# Temperatura_y_humedadC.net
KiCad netlist of a schematic drawn in EAGLE
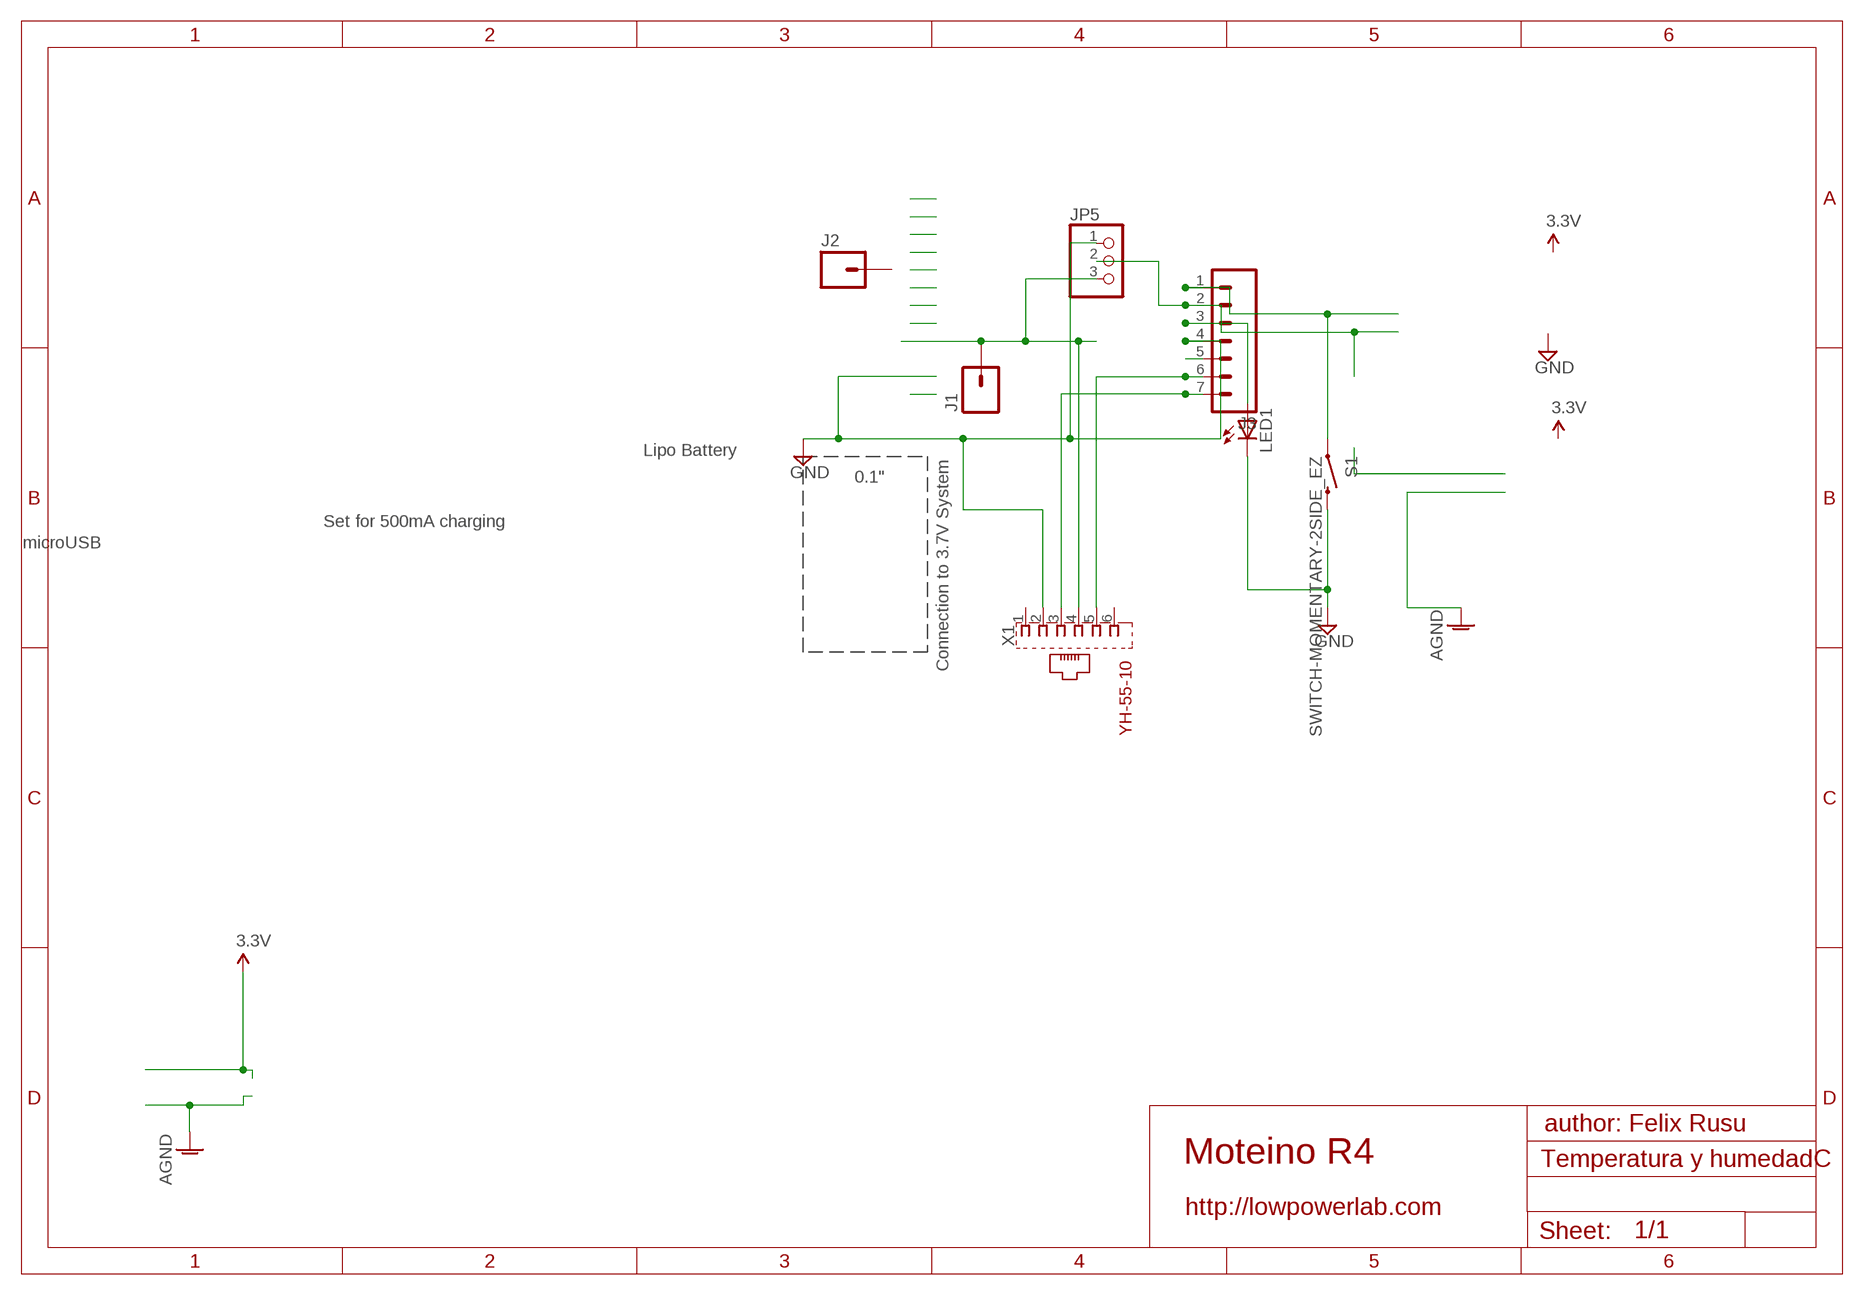
[diagram p0: schematic, sheet 1]

(export (version "E")
  (design (tool "Eeschema 10.0.6"))
  (components
    (comp (ref "J1")
      (value "M01PTH")
      (footprint "eagle-import:1X01")
      (libsource (lib "eagle-import") (part "M01PTH"))
    )
    (comp (ref "J2")
      (value "M01PTH")
      (footprint "eagle-import:1X01")
      (libsource (lib "eagle-import") (part "M01PTH"))
    )
    (comp (ref "J3")
      (value "M07")
      (footprint "eagle-import:1X07")
      (libsource (lib "eagle-import") (part "M07"))
    )
    (comp (ref "JP5")
      (value "PINHD-1X3")
      (footprint "eagle-import:1X03")
      (libsource (lib "eagle-import") (part "PINHD-1X3"))
    )
    (comp (ref "LED1")
      (value "LED3MM")
      (footprint "eagle-import:LED3MM")
      (libsource (lib "eagle-import") (part "LED3MM"))
    )
    (comp (ref "S1")
      (value "SWITCH-MOMENTARY-2SIDE_EZ")
      (footprint "eagle-import:TACTILE-PTH-SIDEEZ")
      (libsource (lib "eagle-import") (part "SWITCH-MOMENTARY-2SIDE_EZ"))
    )
    (comp (ref "X1")
      (value "YH-55-10")
      (footprint "eagle-import:YH-55-10")
      (libsource (lib "eagle-import") (part "YH-55-10"))
    )
  )
  (nets
    (net (code "3") (name "GND") (class "Default")
      (node (ref "J3") (pin "4") (pinfunction "4_4") (pintype "passive"))
      (node (ref "JP5") (pin "1") (pinfunction "1_1") (pintype "passive"))
      (node (ref "LED1") (pin "K") (pinfunction "C_K") (pintype "passive"))
      (node (ref "S1") (pin "2") (pinfunction "2_2") (pintype "passive"))
      (node (ref "X1") (pin "2") (pinfunction "2_2") (pintype "passive"))
    )
    (net (code "4") (name "Net-(J1-Pad1)") (class "Default")
      (node (ref "J1") (pin "1") (pinfunction "1_1") (pintype "passive"))
      (node (ref "JP5") (pin "3") (pinfunction "3_3") (pintype "passive"))
      (node (ref "X1") (pin "4") (pinfunction "4_4") (pintype "passive"))
    )
    (net (code "5") (name "Net-(J3-Pad1)") (class "Default")
      (node (ref "J3") (pin "1") (pinfunction "1_1") (pintype "passive"))
      (node (ref "S1") (pin "1") (pinfunction "1_1") (pintype "passive"))
    )
    (net (code "6") (name "Net-(J3-Pad2)") (class "Default")
      (node (ref "J3") (pin "2") (pinfunction "2_2") (pintype "passive"))
      (node (ref "JP5") (pin "2") (pinfunction "2_2") (pintype "passive"))
    )
    (net (code "7") (name "Net-(J3-Pad3)") (class "Default")
      (node (ref "J3") (pin "3") (pinfunction "3_3") (pintype "passive"))
      (node (ref "LED1") (pin "A") (pinfunction "A_A") (pintype "passive"))
    )
    (net (code "8") (name "Net-(J3-Pad6)") (class "Default")
      (node (ref "J3") (pin "6") (pinfunction "6_6") (pintype "passive"))
      (node (ref "X1") (pin "5") (pinfunction "5_5") (pintype "passive"))
    )
    (net (code "9") (name "Net-(J3-Pad7)") (class "Default")
      (node (ref "J3") (pin "7") (pinfunction "7_7") (pintype "passive"))
      (node (ref "X1") (pin "3") (pinfunction "3_3") (pintype "passive"))
    )
    (net (code "10") (name "unconnected-(J2-Pad1)") (class "Default")
      (node (ref "J2") (pin "1") (pinfunction "1_1") (pintype "passive"))
    )
    (net (code "11") (name "unconnected-(J3-Pad5)") (class "Default")
      (node (ref "J3") (pin "5") (pinfunction "5_5") (pintype "passive"))
    )
    (net (code "12") (name "unconnected-(X1-Pad1)") (class "Default")
      (node (ref "X1") (pin "1") (pinfunction "1_1") (pintype "passive"))
    )
    (net (code "13") (name "unconnected-(X1-Pad6)") (class "Default")
      (node (ref "X1") (pin "6") (pinfunction "6_6") (pintype "passive"))
    )
  )
)
